# 11-MT7688AN_RF_Front_End.net
KiCad netlist of a schematic drawn in Altium Designer
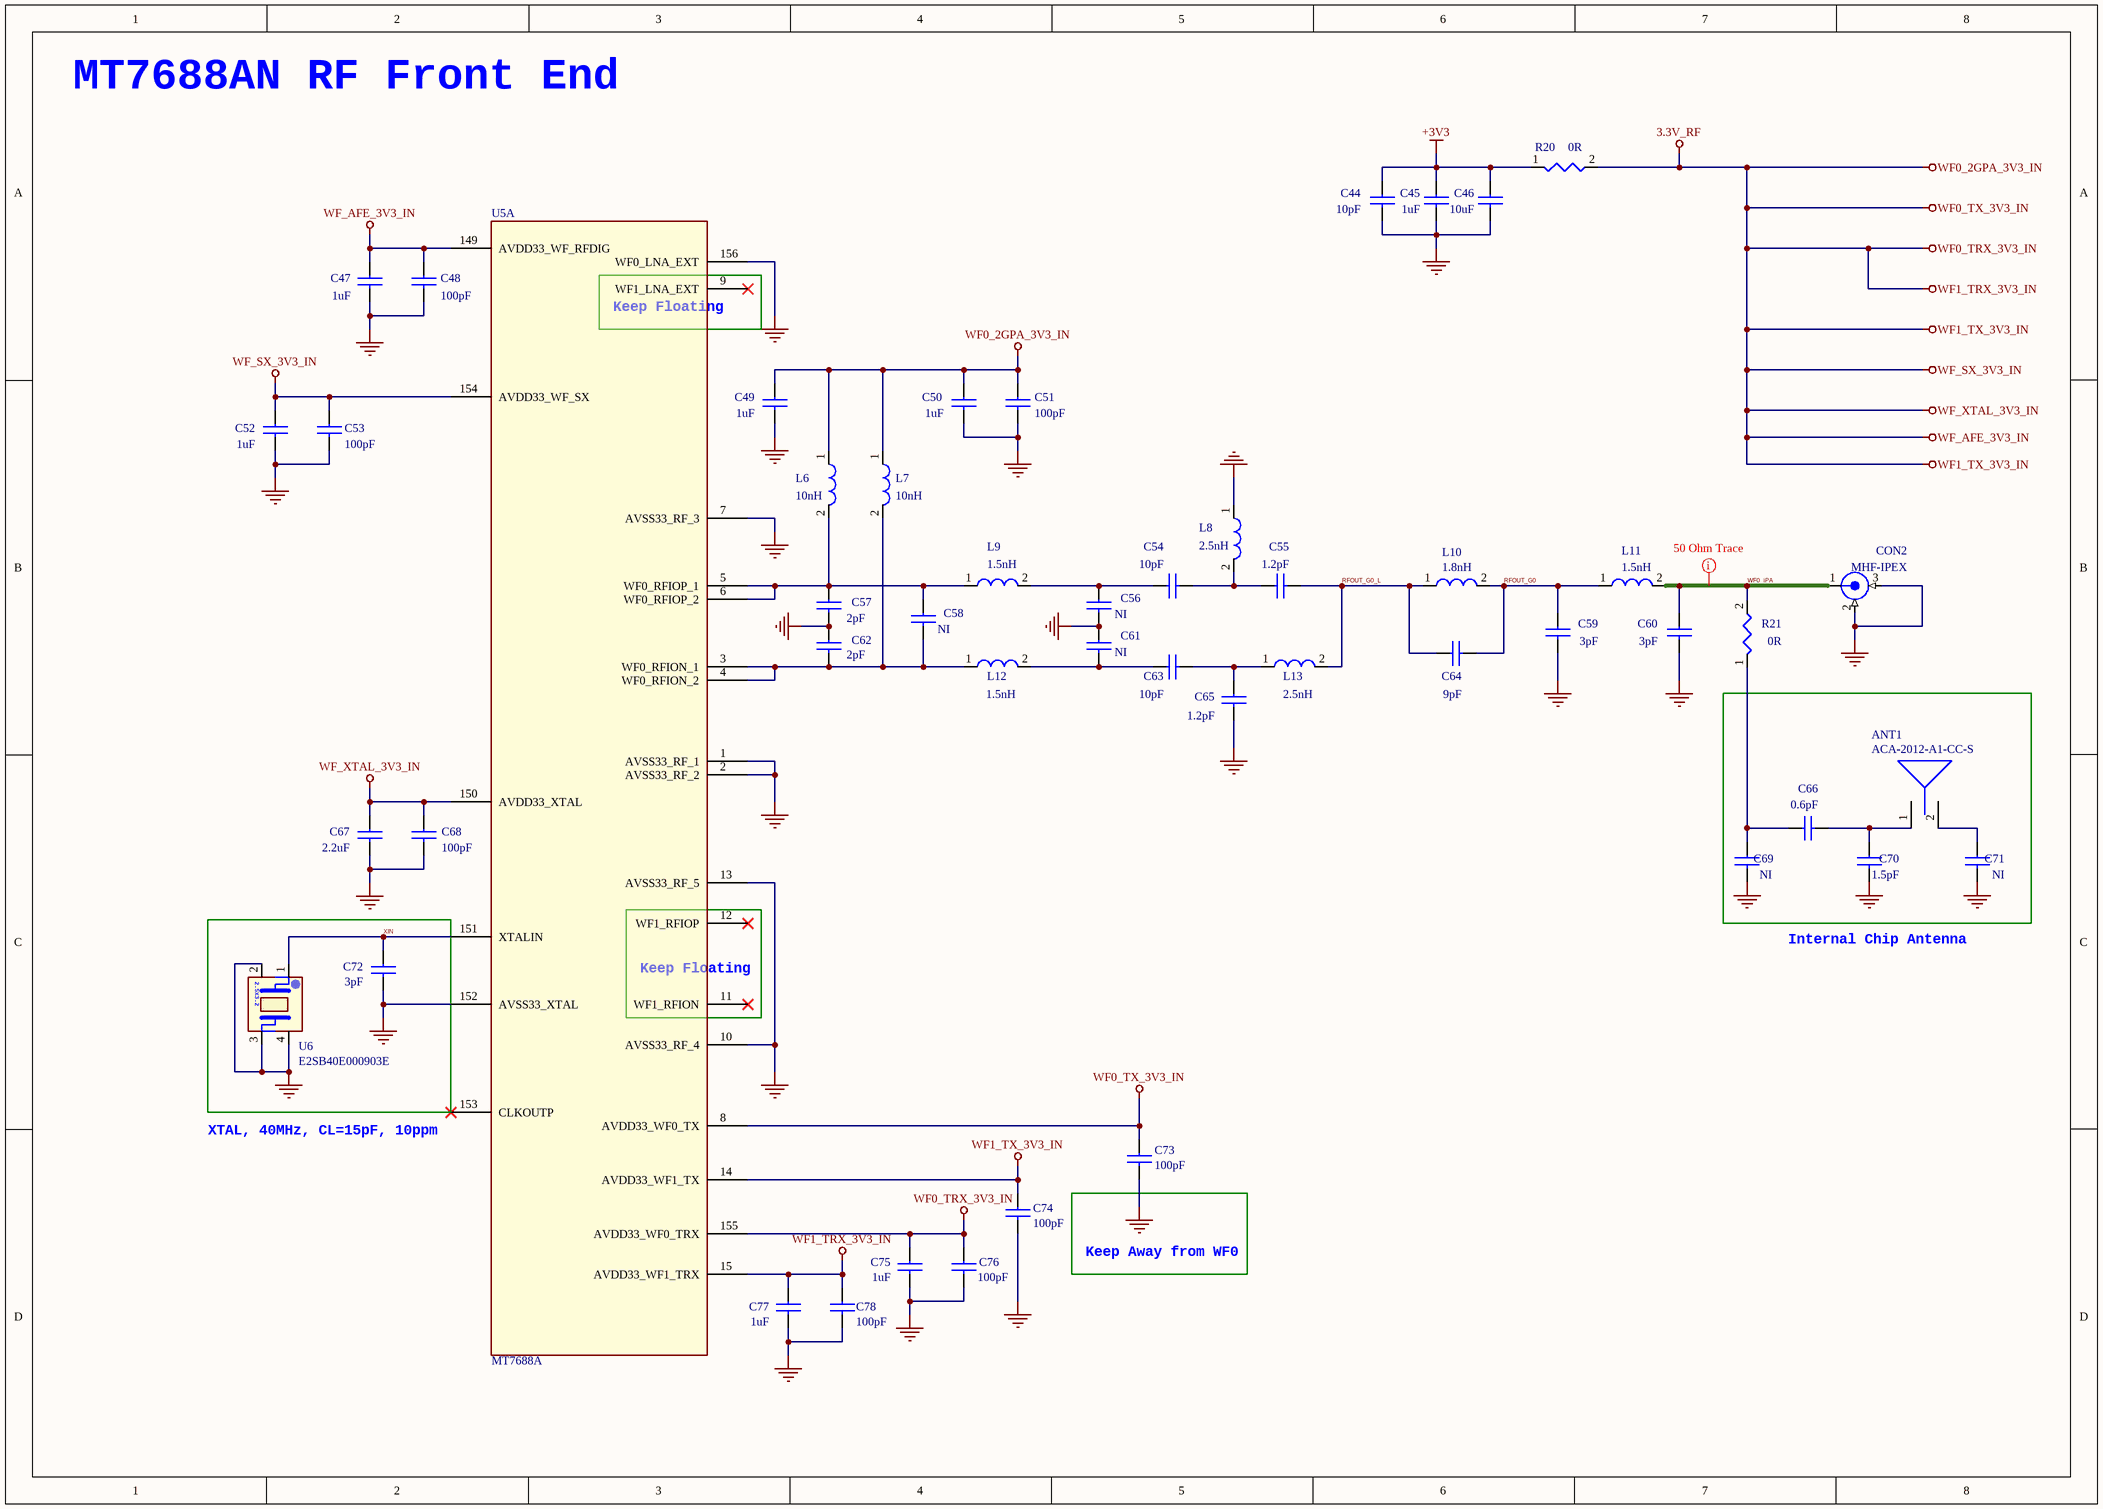
[diagram p0: 11-MT7688AN RF Front End.SchDoc]

(export (version "E")
  (design (tool "Eeschema 10.0.6"))
  (components
    (comp (ref "ANT1")
      (value "ACA-2012-A1-CC-S")
      (footprint "ACA-2012A")
      (libsource (lib "MT7688AN") (part "Antenna_2012"))
    )
    (comp (ref "C44")
      (value "10pF")
      (footprint "CAPC1005X60X30NL05T10")
      (libsource (lib "MT7688AN") (part "CAP NP"))
    )
    (comp (ref "C45")
      (value "1uF")
      (footprint "CAPC1608X90X35NL10T15")
      (libsource (lib "MT7688AN") (part "CAP NP"))
    )
    (comp (ref "C46")
      (value "10uF")
      (footprint "CAPC1608X90X35NL10T15")
      (libsource (lib "MT7688AN") (part "CAP NP"))
    )
    (comp (ref "C47")
      (value "1uF")
      (footprint "CAPC1608X90X35NL10T15")
      (libsource (lib "MT7688AN") (part "CAP NP"))
    )
    (comp (ref "C48")
      (value "100pF")
      (footprint "CAPC1005X60X30NL05T10")
      (libsource (lib "MT7688AN") (part "CAP NP"))
    )
    (comp (ref "C49")
      (value "1uF")
      (footprint "CAPC1005X60X30NL05T10")
      (libsource (lib "MT7688AN") (part "CAP NP"))
    )
    (comp (ref "C50")
      (value "1uF")
      (footprint "CAPC1005X60X30NL05T10")
      (libsource (lib "MT7688AN") (part "CAP NP"))
    )
    (comp (ref "C51")
      (value "100pF")
      (footprint "CAPC1005X60X30NL05T10")
      (libsource (lib "MT7688AN") (part "CAP NP"))
    )
    (comp (ref "C52")
      (value "1uF")
      (footprint "CAPC1608X90X35NL10T15")
      (libsource (lib "MT7688AN") (part "CAP NP"))
    )
    (comp (ref "C53")
      (value "100pF")
      (footprint "CAPC1005X60X30NL05T10")
      (libsource (lib "MT7688AN") (part "CAP NP"))
    )
    (comp (ref "C54")
      (value "10pF")
      (footprint "CAPC1005X60X30NL05T10")
      (libsource (lib "MT7688AN") (part "CAP NP"))
    )
    (comp (ref "C55")
      (value "1.2pF")
      (footprint "CAPC1005X60X30NL05T10")
      (libsource (lib "MT7688AN") (part "CAP NP"))
    )
    (comp (ref "C56")
      (value "NI")
      (footprint "CAPC1005X60X30NL05T10")
      (libsource (lib "MT7688AN") (part "CAP NP"))
    )
    (comp (ref "C57")
      (value "2pF")
      (footprint "CAPC1005X60X30NL05T10")
      (libsource (lib "MT7688AN") (part "CAP NP"))
    )
    (comp (ref "C58")
      (value "NI")
      (footprint "CAPC1005X60X30NL05T10")
      (libsource (lib "MT7688AN") (part "CAP NP"))
    )
    (comp (ref "C59")
      (value "3pF")
      (footprint "CAPC1005X60X30NL05T10")
      (libsource (lib "MT7688AN") (part "CAP NP"))
    )
    (comp (ref "C60")
      (value "3pF")
      (footprint "CAPC1005X60X30NL05T10")
      (libsource (lib "MT7688AN") (part "CAP NP"))
    )
    (comp (ref "C61")
      (value "NI")
      (footprint "CAPC1005X60X30NL05T10")
      (libsource (lib "MT7688AN") (part "CAP NP"))
    )
    (comp (ref "C62")
      (value "2pF")
      (footprint "CAPC1005X60X30NL05T10")
      (libsource (lib "MT7688AN") (part "CAP NP"))
    )
    (comp (ref "C63")
      (value "10pF")
      (footprint "CAPC1005X60X30NL05T10")
      (libsource (lib "MT7688AN") (part "CAP NP"))
    )
    (comp (ref "C64")
      (value "9pF")
      (footprint "CAPC1005X60X30NL05T10")
      (libsource (lib "MT7688AN") (part "CAP NP"))
    )
    (comp (ref "C65")
      (value "1.2pF")
      (footprint "CAPC1005X60X30NL05T10")
      (libsource (lib "MT7688AN") (part "CAP NP"))
    )
    (comp (ref "C66")
      (value "0.6pF")
      (footprint "CAPC1005X60X30NL05T10")
      (libsource (lib "MT7688AN") (part "CAP NP"))
    )
    (comp (ref "C67")
      (value "2.2uF")
      (footprint "CAPC1608X90X35NL10T15")
      (libsource (lib "MT7688AN") (part "CAP NP"))
    )
    (comp (ref "C68")
      (value "100pF")
      (footprint "CAPC1005X60X30NL05T10")
      (libsource (lib "MT7688AN") (part "CAP NP"))
    )
    (comp (ref "C69")
      (value "NI")
      (footprint "CAPC1005X60X30NL05T10")
      (libsource (lib "MT7688AN") (part "CAP NP"))
    )
    (comp (ref "C70")
      (value "1.5pF")
      (footprint "CAPC1005X60X30NL05T10")
      (libsource (lib "MT7688AN") (part "CAP NP"))
    )
    (comp (ref "C71")
      (value "NI")
      (footprint "CAPC1005X60X30NL05T10")
      (libsource (lib "MT7688AN") (part "CAP NP"))
    )
    (comp (ref "C72")
      (value "3pF")
      (footprint "CAPC1005X60X30NL05T10")
      (libsource (lib "MT7688AN") (part "CAP NP"))
    )
    (comp (ref "C73")
      (value "100pF")
      (footprint "CAPC1005X60X30NL05T10")
      (libsource (lib "MT7688AN") (part "CAP NP"))
    )
    (comp (ref "C74")
      (value "100pF")
      (footprint "CAPC1005X60X30NL05T10")
      (libsource (lib "MT7688AN") (part "CAP NP"))
    )
    (comp (ref "C75")
      (value "1uF")
      (footprint "CAPC1608X90X35NL10T15")
      (libsource (lib "MT7688AN") (part "CAP NP"))
    )
    (comp (ref "C76")
      (value "100pF")
      (footprint "CAPC1005X60X30NL05T10")
      (libsource (lib "MT7688AN") (part "CAP NP"))
    )
    (comp (ref "C77")
      (value "1uF")
      (footprint "CAPC1608X90X35NL10T15")
      (libsource (lib "MT7688AN") (part "CAP NP"))
    )
    (comp (ref "C78")
      (value "100pF")
      (footprint "CAPC1005X60X30NL05T10")
      (libsource (lib "MT7688AN") (part "CAP NP"))
    )
    (comp (ref "CON2")
      (value "MHF-IPEX")
      (footprint "I-PEX CON")
      (libsource (lib "MT7688AN") (part "SMA/UFLR"))
    )
    (comp (ref "L6")
      (value "10nH")
      (footprint "CAPC1005X60X30NL05T10")
      (libsource (lib "MT7688AN") (part "L/0402"))
    )
    (comp (ref "L7")
      (value "10nH")
      (footprint "CAPC1005X60X30NL05T10")
      (libsource (lib "MT7688AN") (part "L/0402"))
    )
    (comp (ref "L8")
      (value "2.5nH")
      (footprint "CAPC1005X60X30NL05T10")
      (libsource (lib "MT7688AN") (part "L/0402"))
    )
    (comp (ref "L9")
      (value "1.5nH")
      (footprint "CAPC1005X60X30NL05T10")
      (description "LQP03TN1N5B02D")
      (libsource (lib "MT7688AN") (part "L/0402"))
    )
    (comp (ref "L10")
      (value "1.8nH")
      (footprint "CAPC1005X60X30NL05T10")
      (libsource (lib "MT7688AN") (part "L/0402"))
    )
    (comp (ref "L11")
      (value "1.5nH")
      (footprint "CAPC1005X60X30NL05T10")
      (description "LQP03TN1N5B02D")
      (libsource (lib "MT7688AN") (part "L/0402"))
    )
    (comp (ref "L12")
      (value "1.5nH")
      (footprint "CAPC1005X60X30NL05T10")
      (description "LQP03TN1N5B02D")
      (libsource (lib "MT7688AN") (part "L/0402"))
    )
    (comp (ref "L13")
      (value "2.5nH")
      (footprint "CAPC1005X60X30NL05T10")
      (libsource (lib "MT7688AN") (part "L/0402"))
    )
    (comp (ref "R20")
      (value "0R")
      (footprint "RESC1609X50X30LL10T20")
      (libsource (lib "MT7688AN") (part "RES/0402_3"))
    )
    (comp (ref "R21")
      (value "0R")
      (footprint "RESC1005X40X25NL05T05")
      (libsource (lib "MT7688AN") (part "RES/0402_3"))
    )
    (comp (ref "U5")
      (value "MT7688A")
      (footprint "MT7628AN12X12")
      (libsource (lib "MT7688AN") (part "MT7620N-n_26"))
    )
    (comp (ref "U6")
      (value "E2SB40E000903E")
      (footprint "XTAL 2520")
      (description "XTAL, 40MHz, CL=15pF, 10ppm, -30~+85C")
      (libsource (lib "MT7688AN") (part "XTAL_3.2x2.5"))
    )
  )
  (nets
    (net (code "1") (name "+3V3") (class "Default")
      (node (ref "C44") (pin "1") (pinfunction "1_1") (pintype "passive"))
      (node (ref "C45") (pin "1") (pinfunction "1_1") (pintype "passive"))
      (node (ref "C46") (pin "1") (pinfunction "1_1") (pintype "passive"))
      (node (ref "R20") (pin "1") (pinfunction "1_1") (pintype "passive"))
    )
    (net (code "2") (name "/RFOUT_G0") (class "Default")
      (node (ref "C59") (pin "1") (pinfunction "1_1") (pintype "passive"))
      (node (ref "C64") (pin "2") (pinfunction "2_2") (pintype "passive"))
      (node (ref "L10") (pin "2") (pinfunction "2_2") (pintype "passive"))
      (node (ref "L11") (pin "1") (pinfunction "1_1") (pintype "passive"))
    )
    (net (code "3") (name "/RFOUT_G0_L") (class "Default")
      (node (ref "C55") (pin "2") (pinfunction "2_2") (pintype "passive"))
      (node (ref "C64") (pin "1") (pinfunction "1_1") (pintype "passive"))
      (node (ref "L10") (pin "1") (pinfunction "1_1") (pintype "passive"))
      (node (ref "L13") (pin "2") (pinfunction "2_2") (pintype "passive"))
    )
    (net (code "4") (name "/WF0_iPA") (class "Default")
      (node (ref "C60") (pin "1") (pinfunction "1_1") (pintype "passive"))
      (node (ref "CON2") (pin "1") (pinfunction "1_1") (pintype "passive"))
      (node (ref "L11") (pin "2") (pinfunction "2_2") (pintype "passive"))
      (node (ref "R21") (pin "2") (pinfunction "2_2") (pintype "passive"))
    )
    (net (code "5") (name "/XIN") (class "Default")
      (node (ref "C72") (pin "1") (pinfunction "1_1") (pintype "passive"))
      (node (ref "U5") (pin "151") (pinfunction "XTALIN_151") (pintype "passive"))
      (node (ref "U6") (pin "1") (pinfunction "X1_1") (pintype "passive"))
    )
    (net (code "6") (name "3.3V_RF") (class "Default")
      (node (ref "C47") (pin "1") (pinfunction "1_1") (pintype "passive"))
      (node (ref "C48") (pin "1") (pinfunction "1_1") (pintype "passive"))
      (node (ref "C49") (pin "1") (pinfunction "1_1") (pintype "passive"))
      (node (ref "C50") (pin "1") (pinfunction "1_1") (pintype "passive"))
      (node (ref "C51") (pin "1") (pinfunction "1_1") (pintype "passive"))
      (node (ref "C52") (pin "1") (pinfunction "1_1") (pintype "passive"))
      (node (ref "C53") (pin "1") (pinfunction "1_1") (pintype "passive"))
      (node (ref "C67") (pin "1") (pinfunction "1_1") (pintype "passive"))
      (node (ref "C68") (pin "1") (pinfunction "1_1") (pintype "passive"))
      (node (ref "C73") (pin "1") (pinfunction "1_1") (pintype "passive"))
      (node (ref "C74") (pin "1") (pinfunction "1_1") (pintype "passive"))
      (node (ref "C75") (pin "1") (pinfunction "1_1") (pintype "passive"))
      (node (ref "C76") (pin "1") (pinfunction "1_1") (pintype "passive"))
      (node (ref "C77") (pin "1") (pinfunction "1_1") (pintype "passive"))
      (node (ref "C78") (pin "1") (pinfunction "1_1") (pintype "passive"))
      (node (ref "L6") (pin "1") (pinfunction "1_1") (pintype "passive"))
      (node (ref "L7") (pin "1") (pinfunction "1_1") (pintype "passive"))
      (node (ref "R20") (pin "2") (pinfunction "2_2") (pintype "passive"))
      (node (ref "U5") (pin "14") (pinfunction "AVDD33_WF1_TX_14") (pintype "power_in"))
      (node (ref "U5") (pin "149") (pinfunction "AVDD33_WF_RFDIG_149") (pintype "power_in"))
      (node (ref "U5") (pin "15") (pinfunction "AVDD33_WF1_TRX_15") (pintype "power_in"))
      (node (ref "U5") (pin "150") (pinfunction "AVDD33_XTAL_150") (pintype "power_in"))
      (node (ref "U5") (pin "154") (pinfunction "AVDD33_WF_SX_154") (pintype "power_in"))
      (node (ref "U5") (pin "155") (pinfunction "AVDD33_WF0_TRX_155") (pintype "power_in"))
      (node (ref "U5") (pin "8") (pinfunction "AVDD33_WF0_TX_8") (pintype "power_in"))
    )
    (net (code "7") (name "GND") (class "Default")
      (node (ref "C44") (pin "2") (pinfunction "2_2") (pintype "passive"))
      (node (ref "C45") (pin "2") (pinfunction "2_2") (pintype "passive"))
      (node (ref "C46") (pin "2") (pinfunction "2_2") (pintype "passive"))
      (node (ref "C47") (pin "2") (pinfunction "2_2") (pintype "passive"))
      (node (ref "C48") (pin "2") (pinfunction "2_2") (pintype "passive"))
      (node (ref "C49") (pin "2") (pinfunction "2_2") (pintype "passive"))
      (node (ref "C50") (pin "2") (pinfunction "2_2") (pintype "passive"))
      (node (ref "C51") (pin "2") (pinfunction "2_2") (pintype "passive"))
      (node (ref "C52") (pin "2") (pinfunction "2_2") (pintype "passive"))
      (node (ref "C53") (pin "2") (pinfunction "2_2") (pintype "passive"))
      (node (ref "C56") (pin "2") (pinfunction "2_2") (pintype "passive"))
      (node (ref "C57") (pin "2") (pinfunction "2_2") (pintype "passive"))
      (node (ref "C59") (pin "2") (pinfunction "2_2") (pintype "passive"))
      (node (ref "C60") (pin "2") (pinfunction "2_2") (pintype "passive"))
      (node (ref "C61") (pin "1") (pinfunction "1_1") (pintype "passive"))
      (node (ref "C62") (pin "1") (pinfunction "1_1") (pintype "passive"))
      (node (ref "C65") (pin "2") (pinfunction "2_2") (pintype "passive"))
      (node (ref "C67") (pin "2") (pinfunction "2_2") (pintype "passive"))
      (node (ref "C68") (pin "2") (pinfunction "2_2") (pintype "passive"))
      (node (ref "C69") (pin "2") (pinfunction "2_2") (pintype "passive"))
      (node (ref "C70") (pin "2") (pinfunction "2_2") (pintype "passive"))
      (node (ref "C71") (pin "2") (pinfunction "2_2") (pintype "passive"))
      (node (ref "C72") (pin "2") (pinfunction "2_2") (pintype "passive"))
      (node (ref "C73") (pin "2") (pinfunction "2_2") (pintype "passive"))
      (node (ref "C74") (pin "2") (pinfunction "2_2") (pintype "passive"))
      (node (ref "C75") (pin "2") (pinfunction "2_2") (pintype "passive"))
      (node (ref "C76") (pin "2") (pinfunction "2_2") (pintype "passive"))
      (node (ref "C77") (pin "2") (pinfunction "2_2") (pintype "passive"))
      (node (ref "C78") (pin "2") (pinfunction "2_2") (pintype "passive"))
      (node (ref "CON2") (pin "2") (pinfunction "2_2") (pintype "input"))
      (node (ref "CON2") (pin "3") (pinfunction "GNDA_3") (pintype "input"))
      (node (ref "L8") (pin "1") (pinfunction "1_1") (pintype "passive"))
      (node (ref "U5") (pin "1") (pinfunction "AVSS33_RF_1_1") (pintype "passive"))
      (node (ref "U5") (pin "10") (pinfunction "AVSS33_RF_4_10") (pintype "passive"))
      (node (ref "U5") (pin "13") (pinfunction "AVSS33_RF_5_13") (pintype "passive"))
      (node (ref "U5") (pin "152") (pinfunction "AVSS33_XTAL_152") (pintype "passive"))
      (node (ref "U5") (pin "156") (pinfunction "WF0_LNA_EXT_156") (pintype "passive"))
      (node (ref "U5") (pin "2") (pinfunction "AVSS33_RF_2_2") (pintype "passive"))
      (node (ref "U5") (pin "7") (pinfunction "AVSS33_RF_3_7") (pintype "passive"))
      (node (ref "U6") (pin "2") (pinfunction "NC_2") (pintype "passive"))
      (node (ref "U6") (pin "3") (pinfunction "X2_3") (pintype "passive"))
      (node (ref "U6") (pin "4") (pinfunction "NC_4") (pintype "passive"))
    )
    (net (code "8") (name "Net-(ANT1-IN)") (class "Default")
      (node (ref "ANT1") (pin "1") (pinfunction "IN_1") (pintype "passive"))
      (node (ref "C66") (pin "2") (pinfunction "2_2") (pintype "passive"))
      (node (ref "C70") (pin "1") (pinfunction "1_1") (pintype "passive"))
    )
    (net (code "9") (name "Net-(ANT1-OUT)") (class "Default")
      (node (ref "ANT1") (pin "2") (pinfunction "OUT_2") (pintype "passive"))
      (node (ref "C71") (pin "1") (pinfunction "1_1") (pintype "passive"))
    )
    (net (code "10") (name "Net-(C54-Pad1)") (class "Default")
      (node (ref "C54") (pin "1") (pinfunction "1_1") (pintype "passive"))
      (node (ref "C56") (pin "1") (pinfunction "1_1") (pintype "passive"))
      (node (ref "L9") (pin "2") (pinfunction "2_2") (pintype "passive"))
    )
    (net (code "11") (name "Net-(C54-Pad2)") (class "Default")
      (node (ref "C54") (pin "2") (pinfunction "2_2") (pintype "passive"))
      (node (ref "C55") (pin "1") (pinfunction "1_1") (pintype "passive"))
      (node (ref "L8") (pin "2") (pinfunction "2_2") (pintype "passive"))
    )
    (net (code "12") (name "Net-(C61-Pad2)") (class "Default")
      (node (ref "C61") (pin "2") (pinfunction "2_2") (pintype "passive"))
      (node (ref "C63") (pin "1") (pinfunction "1_1") (pintype "passive"))
      (node (ref "L12") (pin "2") (pinfunction "2_2") (pintype "passive"))
    )
    (net (code "13") (name "Net-(C63-Pad2)") (class "Default")
      (node (ref "C63") (pin "2") (pinfunction "2_2") (pintype "passive"))
      (node (ref "C65") (pin "1") (pinfunction "1_1") (pintype "passive"))
      (node (ref "L13") (pin "1") (pinfunction "1_1") (pintype "passive"))
    )
    (net (code "14") (name "Net-(C66-Pad1)") (class "Default")
      (node (ref "C66") (pin "1") (pinfunction "1_1") (pintype "passive"))
      (node (ref "C69") (pin "1") (pinfunction "1_1") (pintype "passive"))
      (node (ref "R21") (pin "1") (pinfunction "1_1") (pintype "passive"))
    )
    (net (code "15") (name "Net-(U5A-WF0_RFION_1)") (class "Default")
      (node (ref "C58") (pin "2") (pinfunction "2_2") (pintype "passive"))
      (node (ref "C62") (pin "2") (pinfunction "2_2") (pintype "passive"))
      (node (ref "L12") (pin "1") (pinfunction "1_1") (pintype "passive"))
      (node (ref "L7") (pin "2") (pinfunction "2_2") (pintype "passive"))
      (node (ref "U5") (pin "3") (pinfunction "WF0_RFION_1_3") (pintype "passive"))
      (node (ref "U5") (pin "4") (pinfunction "WF0_RFION_2_4") (pintype "passive"))
    )
    (net (code "16") (name "Net-(U5A-WF0_RFIOP_1)") (class "Default")
      (node (ref "C57") (pin "1") (pinfunction "1_1") (pintype "passive"))
      (node (ref "C58") (pin "1") (pinfunction "1_1") (pintype "passive"))
      (node (ref "L6") (pin "2") (pinfunction "2_2") (pintype "passive"))
      (node (ref "L9") (pin "1") (pinfunction "1_1") (pintype "passive"))
      (node (ref "U5") (pin "5") (pinfunction "WF0_RFIOP_1_5") (pintype "passive"))
      (node (ref "U5") (pin "6") (pinfunction "WF0_RFIOP_2_6") (pintype "passive"))
    )
    (net (code "17") (name "unconnected-(U5A-CLKOUTP-Pad153)") (class "Default")
      (node (ref "U5") (pin "153") (pinfunction "CLKOUTP_153") (pintype "passive+no_connect"))
    )
    (net (code "18") (name "unconnected-(U5A-WF1_LNA_EXT-Pad9)") (class "Default")
      (node (ref "U5") (pin "9") (pinfunction "WF1_LNA_EXT_9") (pintype "passive+no_connect"))
    )
    (net (code "19") (name "unconnected-(U5A-WF1_RFION-Pad11)") (class "Default")
      (node (ref "U5") (pin "11") (pinfunction "WF1_RFION_11") (pintype "passive+no_connect"))
    )
    (net (code "20") (name "unconnected-(U5A-WF1_RFIOP-Pad12)") (class "Default")
      (node (ref "U5") (pin "12") (pinfunction "WF1_RFIOP_12") (pintype "passive+no_connect"))
    )
  )
)
